# power_system.net
KiCad netlist of a schematic drawn in EAGLE
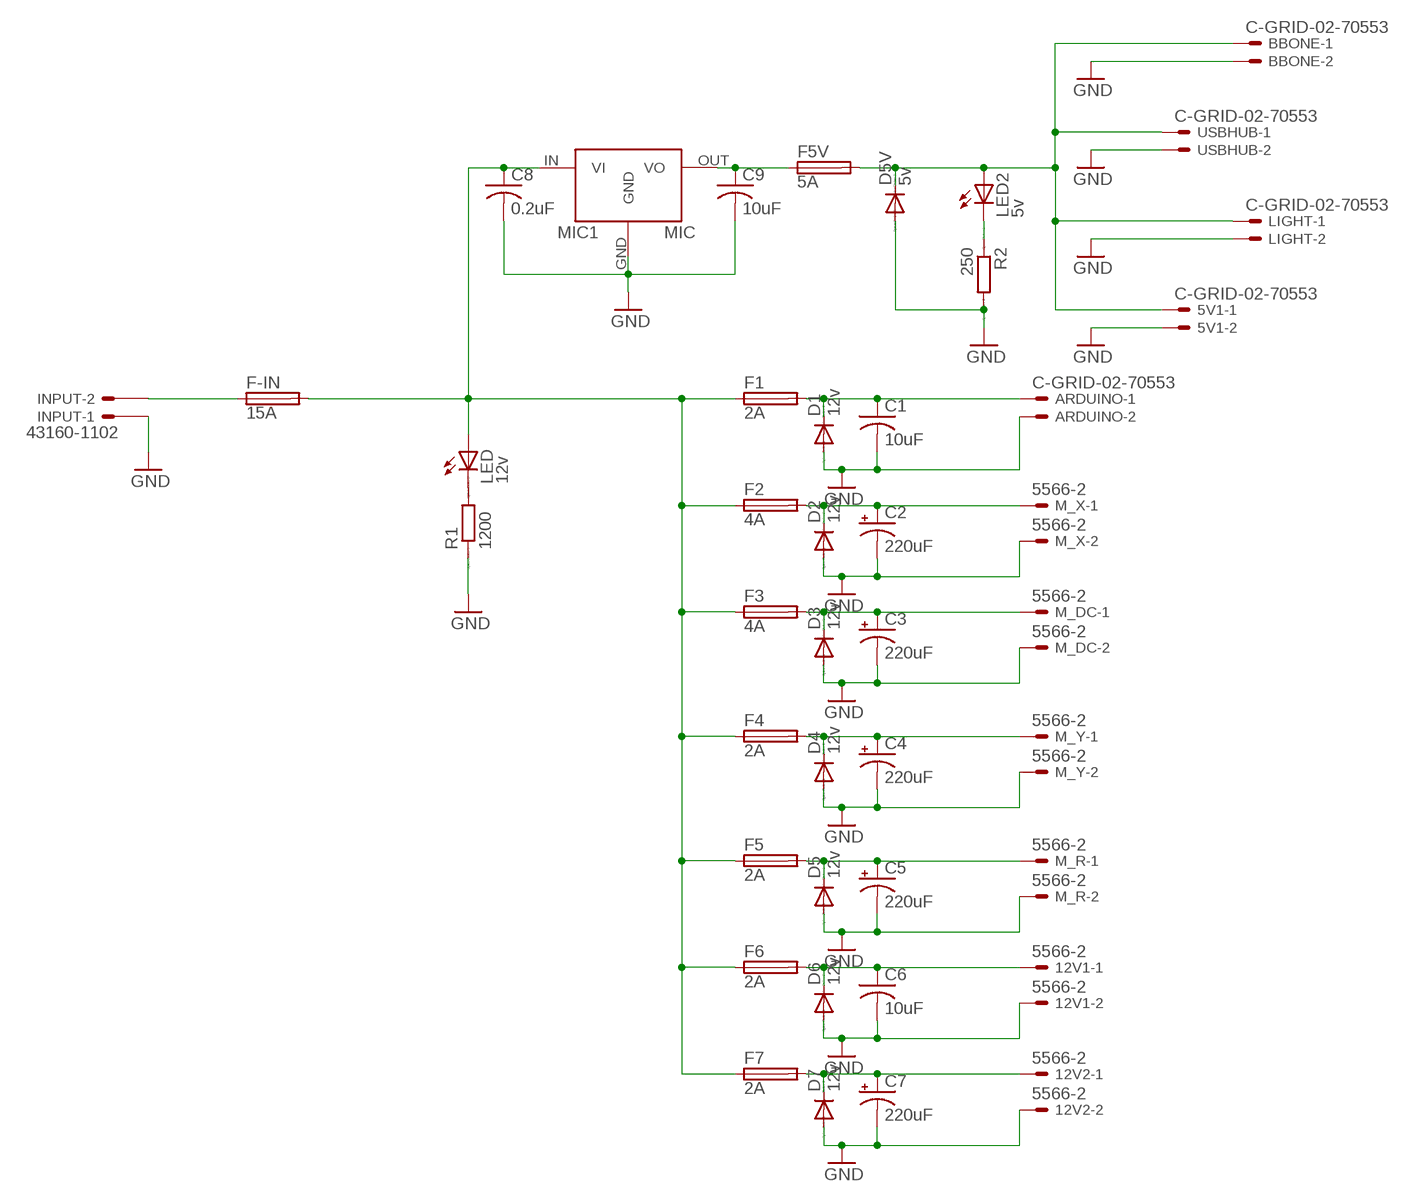
[diagram p0: schematic, sheet 1]

(export (version "E")
  (design (tool "Eeschema 10.0.6"))
  (components
    (comp (ref "5V1")
      (value "C-GRID-02-70553")
      (footprint "eagle-import:70553-02")
      (libsource (lib "eagle-import") (part "C-GRID-02-70553"))
    )
    (comp (ref "12V1")
      (value "5566-2")
      (footprint "eagle-import:5566-2")
      (libsource (lib "eagle-import") (part "5566-2"))
    )
    (comp (ref "12V2")
      (value "5566-2")
      (footprint "eagle-import:5566-2")
      (libsource (lib "eagle-import") (part "5566-2"))
    )
    (comp (ref "ARDUINO")
      (value "C-GRID-02-70553")
      (footprint "eagle-import:70553-02")
      (libsource (lib "eagle-import") (part "C-GRID-02-70553"))
    )
    (comp (ref "BBONE")
      (value "C-GRID-02-70553")
      (footprint "eagle-import:70553-02")
      (libsource (lib "eagle-import") (part "C-GRID-02-70553"))
    )
    (comp (ref "C1")
      (value "10uF")
      (footprint "eagle-import:C1206")
      (libsource (lib "eagle-import") (part "C-USC1206"))
    )
    (comp (ref "C2")
      (value "220uF")
      (footprint "eagle-import:NIPPON_F80")
      (libsource (lib "eagle-import") (part "CAP_POLF80"))
    )
    (comp (ref "C3")
      (value "220uF")
      (footprint "eagle-import:NIPPON_F80")
      (libsource (lib "eagle-import") (part "CAP_POLF80"))
    )
    (comp (ref "C4")
      (value "220uF")
      (footprint "eagle-import:NIPPON_F80")
      (libsource (lib "eagle-import") (part "CAP_POLF80"))
    )
    (comp (ref "C5")
      (value "220uF")
      (footprint "eagle-import:NIPPON_F80")
      (libsource (lib "eagle-import") (part "CAP_POLF80"))
    )
    (comp (ref "C6")
      (value "10uF")
      (footprint "eagle-import:C1206")
      (libsource (lib "eagle-import") (part "C-USC1206"))
    )
    (comp (ref "C7")
      (value "220uF")
      (footprint "eagle-import:NIPPON_F80")
      (libsource (lib "eagle-import") (part "CAP_POLF80"))
    )
    (comp (ref "C8")
      (value "0.2uF")
      (footprint "eagle-import:C1206")
      (libsource (lib "eagle-import") (part "C-USC1206"))
    )
    (comp (ref "C9")
      (value "10uF")
      (footprint "eagle-import:C1206")
      (libsource (lib "eagle-import") (part "C-USC1206"))
    )
    (comp (ref "D1")
      (value "12v")
      (footprint "eagle-import:DO214AC")
      (libsource (lib "eagle-import") (part "DIODE-DO214AC"))
    )
    (comp (ref "D2")
      (value "12v")
      (footprint "eagle-import:DO214AC")
      (libsource (lib "eagle-import") (part "DIODE-DO214AC"))
    )
    (comp (ref "D3")
      (value "12v")
      (footprint "eagle-import:DO214AC")
      (libsource (lib "eagle-import") (part "DIODE-DO214AC"))
    )
    (comp (ref "D4")
      (value "12v")
      (footprint "eagle-import:DO214AC")
      (libsource (lib "eagle-import") (part "DIODE-DO214AC"))
    )
    (comp (ref "D5")
      (value "12v")
      (footprint "eagle-import:DO214AC")
      (libsource (lib "eagle-import") (part "DIODE-DO214AC"))
    )
    (comp (ref "D5V")
      (value "5v")
      (footprint "eagle-import:DO214AC")
      (libsource (lib "eagle-import") (part "DIODE-DO214AC"))
    )
    (comp (ref "D6")
      (value "12v")
      (footprint "eagle-import:DO214AC")
      (libsource (lib "eagle-import") (part "DIODE-DO214AC"))
    )
    (comp (ref "D7")
      (value "12v")
      (footprint "eagle-import:DO214AC")
      (libsource (lib "eagle-import") (part "DIODE-DO214AC"))
    )
    (comp (ref "F-IN")
      (value "15A")
      (footprint "eagle-import:FUSE_HOLDER_5X20MM")
      (libsource (lib "eagle-import") (part "FUSEBLANK_5X20MM"))
    )
    (comp (ref "F1")
      (value "2A")
      (footprint "eagle-import:TE5")
      (libsource (lib "eagle-import") (part "TE5"))
    )
    (comp (ref "F2")
      (value "4A")
      (footprint "eagle-import:TE5")
      (libsource (lib "eagle-import") (part "TE5"))
    )
    (comp (ref "F3")
      (value "4A")
      (footprint "eagle-import:TE5")
      (libsource (lib "eagle-import") (part "TE5"))
    )
    (comp (ref "F4")
      (value "2A")
      (footprint "eagle-import:TE5")
      (libsource (lib "eagle-import") (part "TE5"))
    )
    (comp (ref "F5")
      (value "2A")
      (footprint "eagle-import:TE5")
      (libsource (lib "eagle-import") (part "TE5"))
    )
    (comp (ref "F5V")
      (value "5A")
      (footprint "eagle-import:TE5")
      (libsource (lib "eagle-import") (part "TE5"))
    )
    (comp (ref "F6")
      (value "2A")
      (footprint "eagle-import:TE5")
      (libsource (lib "eagle-import") (part "TE5"))
    )
    (comp (ref "F7")
      (value "2A")
      (footprint "eagle-import:TE5")
      (libsource (lib "eagle-import") (part "TE5"))
    )
    (comp (ref "INPUT")
      (value "43160-1102")
      (footprint "eagle-import:43160-XX02")
      (fields (field (name "MF") "WALDOM/MOLEX"))
      (libsource (lib "eagle-import") (part "43160-0211"))
    )
    (comp (ref "LED")
      (value "12v")
      (footprint "eagle-import:LED5MM")
      (libsource (lib "eagle-import") (part "LED5MM"))
    )
    (comp (ref "LED2")
      (value "5v")
      (footprint "eagle-import:LED5MM")
      (libsource (lib "eagle-import") (part "LED5MM"))
    )
    (comp (ref "LIGHT")
      (value "C-GRID-02-70553")
      (footprint "eagle-import:70553-02")
      (libsource (lib "eagle-import") (part "C-GRID-02-70553"))
    )
    (comp (ref "MIC1")
      (value "MIC29300")
      (footprint "eagle-import:TO220CS")
      (libsource (lib "eagle-import") (part "MIC29300"))
    )
    (comp (ref "M_DC")
      (value "5566-2")
      (footprint "eagle-import:5566-2")
      (libsource (lib "eagle-import") (part "5566-2"))
    )
    (comp (ref "M_R")
      (value "5566-2")
      (footprint "eagle-import:5566-2")
      (libsource (lib "eagle-import") (part "5566-2"))
    )
    (comp (ref "M_X")
      (value "5566-2")
      (footprint "eagle-import:5566-2")
      (libsource (lib "eagle-import") (part "5566-2"))
    )
    (comp (ref "M_Y")
      (value "5566-2")
      (footprint "eagle-import:5566-2")
      (libsource (lib "eagle-import") (part "5566-2"))
    )
    (comp (ref "R1")
      (value "1200")
      (footprint "eagle-import:R1206")
      (libsource (lib "eagle-import") (part "RR1206"))
    )
    (comp (ref "R2")
      (value "250")
      (footprint "eagle-import:R1206")
      (libsource (lib "eagle-import") (part "RR1206"))
    )
    (comp (ref "USBHUB")
      (value "C-GRID-02-70553")
      (footprint "eagle-import:70553-02")
      (libsource (lib "eagle-import") (part "C-GRID-02-70553"))
    )
  )
  (nets
    (net (code "1") (name "GND") (class "Default")
      (node (ref "12V1") (pin "2") (pinfunction "S_2") (pintype "passive"))
      (node (ref "12V2") (pin "2") (pinfunction "S_2") (pintype "passive"))
      (node (ref "5V1") (pin "2") (pinfunction "S_2") (pintype "passive"))
      (node (ref "ARDUINO") (pin "2") (pinfunction "S_2") (pintype "passive"))
      (node (ref "BBONE") (pin "2") (pinfunction "S_2") (pintype "passive"))
      (node (ref "C1") (pin "2") (pinfunction "2_2") (pintype "passive"))
      (node (ref "C2") (pin "-") (pinfunction "-_-") (pintype "passive"))
      (node (ref "C3") (pin "-") (pinfunction "-_-") (pintype "passive"))
      (node (ref "C4") (pin "-") (pinfunction "-_-") (pintype "passive"))
      (node (ref "C5") (pin "-") (pinfunction "-_-") (pintype "passive"))
      (node (ref "C6") (pin "2") (pinfunction "2_2") (pintype "passive"))
      (node (ref "C7") (pin "-") (pinfunction "-_-") (pintype "passive"))
      (node (ref "C8") (pin "2") (pinfunction "2_2") (pintype "passive"))
      (node (ref "C9") (pin "2") (pinfunction "2_2") (pintype "passive"))
      (node (ref "D1") (pin "A") (pinfunction "A_A") (pintype "passive"))
      (node (ref "D2") (pin "A") (pinfunction "A_A") (pintype "passive"))
      (node (ref "D3") (pin "A") (pinfunction "A_A") (pintype "passive"))
      (node (ref "D4") (pin "A") (pinfunction "A_A") (pintype "passive"))
      (node (ref "D5") (pin "A") (pinfunction "A_A") (pintype "passive"))
      (node (ref "D5V") (pin "A") (pinfunction "A_A") (pintype "passive"))
      (node (ref "D6") (pin "A") (pinfunction "A_A") (pintype "passive"))
      (node (ref "D7") (pin "A") (pinfunction "A_A") (pintype "passive"))
      (node (ref "INPUT") (pin "1@1") (pinfunction "S_1@1") (pintype "passive"))
      (node (ref "LIGHT") (pin "2") (pinfunction "S_2") (pintype "passive"))
      (node (ref "MIC1") (pin "GND") (pinfunction "GND_GND") (pintype "bidirectional"))
      (node (ref "M_DC") (pin "2") (pinfunction "S_2") (pintype "passive"))
      (node (ref "M_R") (pin "2") (pinfunction "S_2") (pintype "passive"))
      (node (ref "M_X") (pin "2") (pinfunction "S_2") (pintype "passive"))
      (node (ref "M_Y") (pin "2") (pinfunction "S_2") (pintype "passive"))
      (node (ref "R1") (pin "1") (pinfunction "1_1") (pintype "passive"))
      (node (ref "R2") (pin "2") (pinfunction "2_2") (pintype "passive"))
      (node (ref "USBHUB") (pin "2") (pinfunction "S_2") (pintype "passive"))
    )
    (net (code "2") (name "Net-(5V1A-S)") (class "Default")
      (node (ref "5V1") (pin "1") (pinfunction "S_1") (pintype "passive"))
      (node (ref "BBONE") (pin "1") (pinfunction "S_1") (pintype "passive"))
      (node (ref "D5V") (pin "C") (pinfunction "C_C") (pintype "passive"))
      (node (ref "F5V") (pin "2") (pinfunction "2_2") (pintype "passive"))
      (node (ref "LED2") (pin "A") (pinfunction "A_A") (pintype "passive"))
      (node (ref "LIGHT") (pin "1") (pinfunction "S_1") (pintype "passive"))
      (node (ref "USBHUB") (pin "1") (pinfunction "S_1") (pintype "passive"))
    )
    (net (code "3") (name "Net-(12V1A-S)") (class "Default")
      (node (ref "12V1") (pin "1") (pinfunction "S_1") (pintype "passive"))
      (node (ref "C6") (pin "1") (pinfunction "1_1") (pintype "passive"))
      (node (ref "D6") (pin "C") (pinfunction "C_C") (pintype "passive"))
      (node (ref "F6") (pin "2") (pinfunction "2_2") (pintype "passive"))
    )
    (net (code "4") (name "Net-(12V2A-S)") (class "Default")
      (node (ref "12V2") (pin "1") (pinfunction "S_1") (pintype "passive"))
      (node (ref "C7") (pin "+") (pinfunction "+_+") (pintype "passive"))
      (node (ref "D7") (pin "C") (pinfunction "C_C") (pintype "passive"))
      (node (ref "F7") (pin "2") (pinfunction "2_2") (pintype "passive"))
    )
    (net (code "5") (name "Net-(ARDUINOA-S)") (class "Default")
      (node (ref "ARDUINO") (pin "1") (pinfunction "S_1") (pintype "passive"))
      (node (ref "C1") (pin "1") (pinfunction "1_1") (pintype "passive"))
      (node (ref "D1") (pin "C") (pinfunction "C_C") (pintype "passive"))
      (node (ref "F1") (pin "2") (pinfunction "2_2") (pintype "passive"))
    )
    (net (code "6") (name "Net-(F-IN-Pad1)") (class "Default")
      (node (ref "F-IN") (pin "1") (pinfunction "1_1") (pintype "passive"))
      (node (ref "INPUT") (pin "2@1") (pinfunction "S_2@1") (pintype "passive"))
    )
    (net (code "7") (name "Net-(LED-C)") (class "Default")
      (node (ref "LED") (pin "K") (pinfunction "C_K") (pintype "passive"))
      (node (ref "R1") (pin "2") (pinfunction "2_2") (pintype "passive"))
    )
    (net (code "8") (name "Net-(LED2-C)") (class "Default")
      (node (ref "LED2") (pin "K") (pinfunction "C_K") (pintype "passive"))
      (node (ref "R2") (pin "1") (pinfunction "1_1") (pintype "passive"))
    )
    (net (code "9") (name "Net-(MIC1-VI)") (class "Default")
      (node (ref "C8") (pin "1") (pinfunction "1_1") (pintype "passive"))
      (node (ref "F-IN") (pin "2") (pinfunction "2_2") (pintype "passive"))
      (node (ref "F1") (pin "1") (pinfunction "1_1") (pintype "passive"))
      (node (ref "F2") (pin "1") (pinfunction "1_1") (pintype "passive"))
      (node (ref "F3") (pin "1") (pinfunction "1_1") (pintype "passive"))
      (node (ref "F4") (pin "1") (pinfunction "1_1") (pintype "passive"))
      (node (ref "F5") (pin "1") (pinfunction "1_1") (pintype "passive"))
      (node (ref "F6") (pin "1") (pinfunction "1_1") (pintype "passive"))
      (node (ref "F7") (pin "1") (pinfunction "1_1") (pintype "passive"))
      (node (ref "LED") (pin "A") (pinfunction "A_A") (pintype "passive"))
      (node (ref "MIC1") (pin "IN") (pinfunction "VI_IN") (pintype "bidirectional"))
    )
    (net (code "10") (name "Net-(MIC1-VO)") (class "Default")
      (node (ref "C9") (pin "1") (pinfunction "1_1") (pintype "passive"))
      (node (ref "F5V") (pin "1") (pinfunction "1_1") (pintype "passive"))
      (node (ref "MIC1") (pin "OUT") (pinfunction "VO_OUT") (pintype "bidirectional"))
    )
    (net (code "11") (name "Net-(M_DCA-S)") (class "Default")
      (node (ref "C3") (pin "+") (pinfunction "+_+") (pintype "passive"))
      (node (ref "D3") (pin "C") (pinfunction "C_C") (pintype "passive"))
      (node (ref "F3") (pin "2") (pinfunction "2_2") (pintype "passive"))
      (node (ref "M_DC") (pin "1") (pinfunction "S_1") (pintype "passive"))
    )
    (net (code "12") (name "Net-(M_RA-S)") (class "Default")
      (node (ref "C5") (pin "+") (pinfunction "+_+") (pintype "passive"))
      (node (ref "D5") (pin "C") (pinfunction "C_C") (pintype "passive"))
      (node (ref "F5") (pin "2") (pinfunction "2_2") (pintype "passive"))
      (node (ref "M_R") (pin "1") (pinfunction "S_1") (pintype "passive"))
    )
    (net (code "13") (name "Net-(M_XA-S)") (class "Default")
      (node (ref "C2") (pin "+") (pinfunction "+_+") (pintype "passive"))
      (node (ref "D2") (pin "C") (pinfunction "C_C") (pintype "passive"))
      (node (ref "F2") (pin "2") (pinfunction "2_2") (pintype "passive"))
      (node (ref "M_X") (pin "1") (pinfunction "S_1") (pintype "passive"))
    )
    (net (code "14") (name "Net-(M_YA-S)") (class "Default")
      (node (ref "C4") (pin "+") (pinfunction "+_+") (pintype "passive"))
      (node (ref "D4") (pin "C") (pinfunction "C_C") (pintype "passive"))
      (node (ref "F4") (pin "2") (pinfunction "2_2") (pintype "passive"))
      (node (ref "M_Y") (pin "1") (pinfunction "S_1") (pintype "passive"))
    )
    (net (code "15") (name "unconnected-(INPUTA-S-Pad1@2)") (class "Default")
      (node (ref "INPUT") (pin "1@2") (pinfunction "S_1@2") (pintype "passive"))
    )
    (net (code "16") (name "unconnected-(INPUTB-S-Pad2@2)") (class "Default")
      (node (ref "INPUT") (pin "2@2") (pinfunction "S_2@2") (pintype "passive"))
    )
  )
)
